# Top.net
KiCad netlist of a schematic drawn in Altium Designer
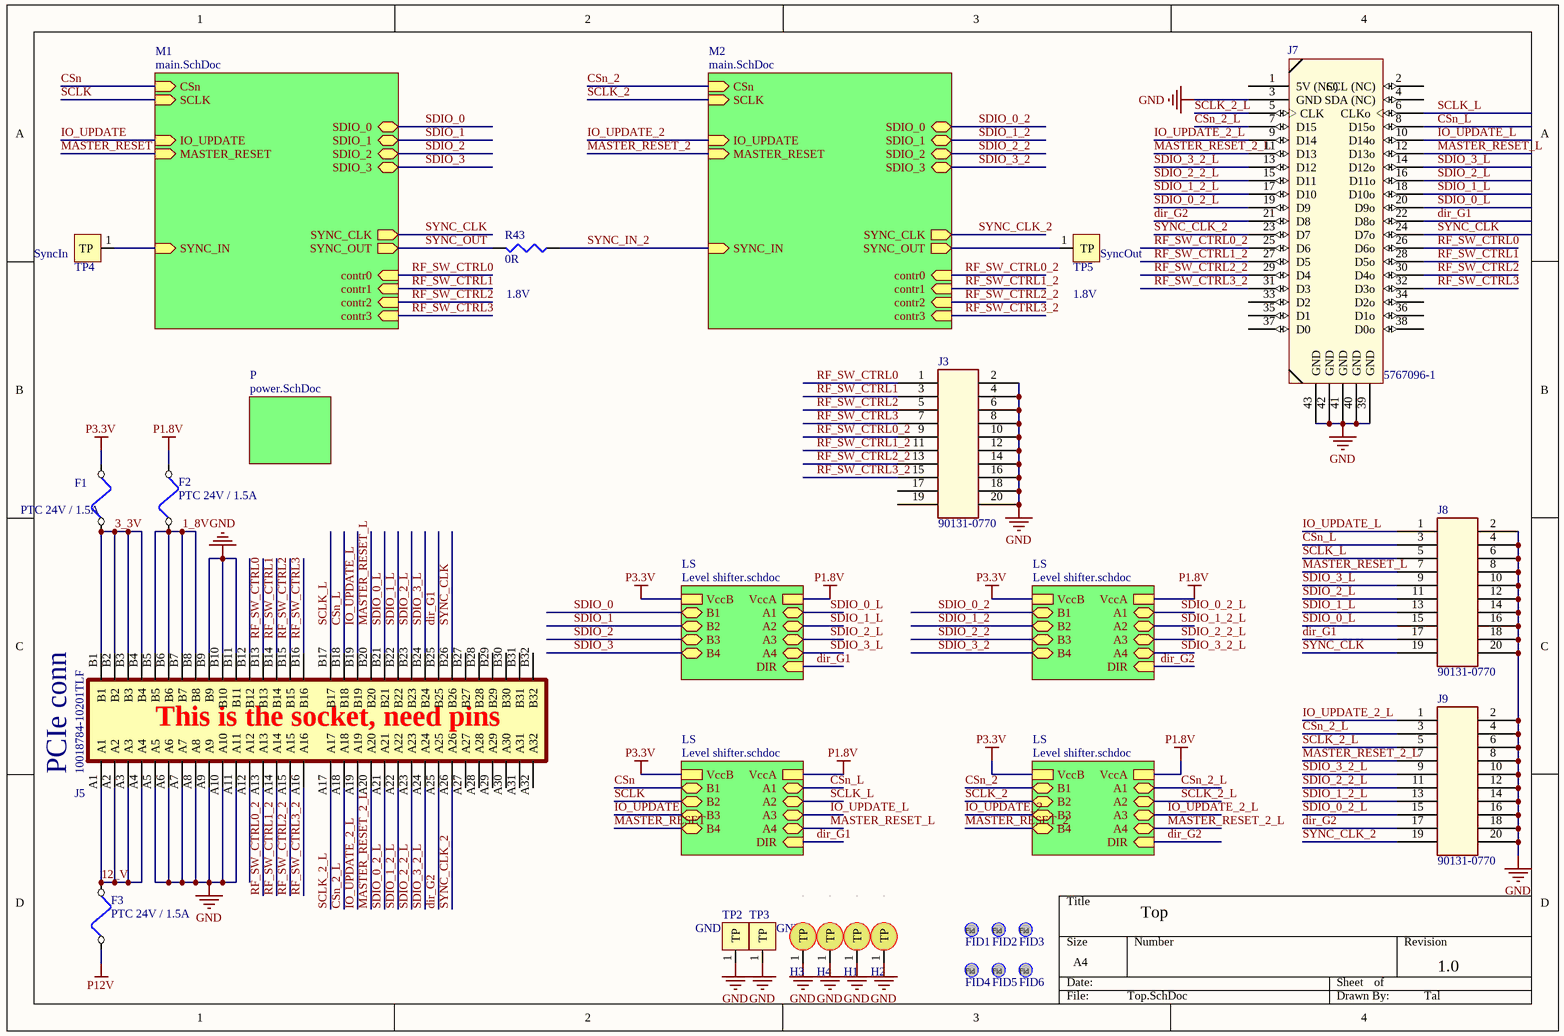
[diagram p0: Top.SchDoc]

(export (version "E")
  (design (tool "Eeschema 10.0.6"))
  (components
    (comp (ref "F1")
      (value "PTC 24V / 1.5A")
      (footprint "Landa_PCB:1812_F")
      (description "FUSE PTC 24V 1.5A POLYFUSE 1812")
      (fields
        (field (name "MANUFACTURER") "Littelfuse Inc")
        (field (name "MANUFACTURER PART NUMBER") "1812L150/24MR")
      )
      (libsource (lib "DPB_spliter") (part "1812L150/24MR"))
    )
    (comp (ref "F2")
      (value "PTC 24V / 1.5A")
      (footprint "Landa_PCB:1812_F")
      (description "FUSE PTC 24V 1.5A POLYFUSE 1812")
      (fields
        (field (name "MANUFACTURER") "Littelfuse Inc")
        (field (name "MANUFACTURER PART NUMBER") "1812L150/24MR")
      )
      (libsource (lib "DPB_spliter") (part "1812L150/24MR"))
    )
    (comp (ref "F3")
      (value "PTC 24V / 1.5A")
      (footprint "Landa_PCB:1812_F")
      (description "FUSE PTC 24V 1.5A POLYFUSE 1812")
      (fields
        (field (name "MANUFACTURER") "Littelfuse Inc")
        (field (name "MANUFACTURER PART NUMBER") "1812L150/24MR")
      )
      (libsource (lib "DPB_spliter") (part "1812L150/24MR"))
    )
    (comp (ref "FID1")
      (value "Fiducial")
      (footprint "Fiducial")
      (libsource (lib "DDS_PCB") (part "Fiducial"))
    )
    (comp (ref "FID2")
      (value "Fiducial")
      (footprint "Fiducial")
      (libsource (lib "DDS_PCB") (part "Fiducial"))
    )
    (comp (ref "FID3")
      (value "Fiducial")
      (footprint "Fiducial")
      (libsource (lib "DDS_PCB") (part "Fiducial"))
    )
    (comp (ref "FID4")
      (value "Fiducial")
      (footprint "Fiducial")
      (libsource (lib "DDS_PCB") (part "Fiducial"))
    )
    (comp (ref "FID5")
      (value "Fiducial")
      (footprint "Fiducial")
      (libsource (lib "DDS_PCB") (part "Fiducial"))
    )
    (comp (ref "FID6")
      (value "Fiducial")
      (footprint "Fiducial")
      (libsource (lib "DDS_PCB") (part "Fiducial"))
    )
    (comp (ref "H1")
      (value "Hole 3mm")
      (footprint "hole 3mm")
      (description "hole 3mm")
      (libsource (lib "L_SCH_Misc") (part "Hole 3mm"))
    )
    (comp (ref "H2")
      (value "Hole 3mm")
      (footprint "hole 3mm")
      (description "hole 3mm")
      (libsource (lib "L_SCH_Misc") (part "Hole 3mm"))
    )
    (comp (ref "H3")
      (value "Hole 3mm")
      (footprint "hole 3mm")
      (description "hole 3mm")
      (libsource (lib "L_SCH_Misc") (part "Hole 3mm"))
    )
    (comp (ref "H4")
      (value "Hole 3mm")
      (footprint "hole 3mm")
      (description "hole 3mm")
      (libsource (lib "L_SCH_Misc") (part "Hole 3mm"))
    )
    (comp (ref "J3")
      (value "90131-0770")
      (footprint "HEADER_10x2")
      (description "CONN HEADER 20 TH")
      (fields
        (field (name "MANUFACTURER") "Molex Connector Corporation")
        (field (name "MANUFACTURER PART NUMBER") "90131-0770")
      )
      (libsource (lib "L_SCH_J_Z") (part "90131-0770"))
    )
    (comp (ref "J5")
      (value "10018784-10201TLF")
      (footprint "PCIE_8LANE_EDGE")
      (description "64 Position Female Connector PCI Expressâ„¢ Gold 0.039 _1.00mm_ Black")
      (fields (field (name "MF") "Amphenol ICC"))
      (libsource (lib "10018784-10201TLF") (part "10018784-10201TLF"))
    )
    (comp (ref "J7")
      (value "5767096-1")
      (footprint "MICTOR-38_PIN")
      (description "CONN MICTOR 38POS .025 VERT SMD")
      (fields
        (field (name "MANUFACTURER") "TE Connectivity")
        (field (name "MANUFACTURER PART NUMBER") "5767096-1")
      )
      (libsource (lib "L_SCH_J_Z") (part "5767096-1"))
    )
    (comp (ref "J8")
      (value "90131-0770")
      (footprint "HEADER_10x2")
      (description "CONN HEADER 20 TH")
      (fields
        (field (name "MANUFACTURER") "Molex Connector Corporation")
        (field (name "MANUFACTURER PART NUMBER") "90131-0770")
      )
      (libsource (lib "L_SCH_J_Z") (part "90131-0770"))
    )
    (comp (ref "J9")
      (value "90131-0770")
      (footprint "HEADER_10x2")
      (description "CONN HEADER 20 TH")
      (fields
        (field (name "MANUFACTURER") "Molex Connector Corporation")
        (field (name "MANUFACTURER PART NUMBER") "90131-0770")
      )
      (libsource (lib "L_SCH_J_Z") (part "90131-0770"))
    )
    (comp (ref "R43")
      (value "0R")
      (footprint "R0402")
      (description "RES 0 OHM 1/10W 1% 0402 SMD")
      (fields
        (field (name "MANUFACTURER PART NUMBER") "ERJ-2RKF1000X")
        (field (name "MANUFACTURER") "Panasonic Electronic Components")
      )
      (libsource (lib "L_SCH_R") (part "RES 100 OHM 1/10W 1% 0402 SMD"))
    )
    (comp (ref "TP2")
      (value "GND")
      (footprint "Landa_PCB:TP_2x1.8")
      (description "TP PC MINIATURE SMT")
      (fields
        (field (name "MANUFACTURER") "Keystone Electronics")
        (field (name "MANUFACTURER PART NUMBER") "5015")
      )
      (libsource (lib "DPB_spliter") (part "TP mini_2"))
    )
    (comp (ref "TP3")
      (value "GND")
      (footprint "Landa_PCB:TP_2x1.8")
      (description "TP PC MINIATURE SMT")
      (fields
        (field (name "MANUFACTURER") "Keystone Electronics")
        (field (name "MANUFACTURER PART NUMBER") "5015")
      )
      (libsource (lib "DPB_spliter") (part "TP mini_1"))
    )
    (comp (ref "TP4")
      (value "SyncIn")
      (footprint "Landa_PCB:TP_2x1.8")
      (description "TP PC MINIATURE SMT")
      (fields
        (field (name "MANUFACTURER") "Keystone Electronics")
        (field (name "MANUFACTURER PART NUMBER") "5015")
      )
      (libsource (lib "") (part "TP mini_2_1"))
    )
    (comp (ref "TP5")
      (value "SyncOut")
      (footprint "Landa_PCB:TP_2x1.8")
      (description "TP PC MINIATURE SMT")
      (fields
        (field (name "MANUFACTURER") "Keystone Electronics")
        (field (name "MANUFACTURER PART NUMBER") "5015")
      )
      (libsource (lib "") (part "TP mini_2_2"))
    )
  )
  (nets
    (net (code "1") (name "/1_8V") (class "Default")
      (node (ref "F2") (pin "1") (pinfunction "1_1") (pintype "passive"))
      (node (ref "J5") (pin "B5") (pinfunction "B5_B5") (pintype "passive"))
      (node (ref "J5") (pin "B6") (pinfunction "B6_B6") (pintype "passive"))
      (node (ref "J5") (pin "B7") (pinfunction "B7_B7") (pintype "passive"))
      (node (ref "J5") (pin "B8") (pinfunction "B8_B8") (pintype "passive"))
    )
    (net (code "2") (name "/3_3V") (class "Default")
      (node (ref "F1") (pin "1") (pinfunction "1_1") (pintype "passive"))
      (node (ref "J5") (pin "B1") (pinfunction "B1_B1") (pintype "passive"))
      (node (ref "J5") (pin "B2") (pinfunction "B2_B2") (pintype "passive"))
      (node (ref "J5") (pin "B3") (pinfunction "B3_B3") (pintype "passive"))
      (node (ref "J5") (pin "B4") (pinfunction "B4_B4") (pintype "passive"))
    )
    (net (code "3") (name "/12_V") (class "Default")
      (node (ref "F3") (pin "2") (pinfunction "2_2") (pintype "passive"))
      (node (ref "J5") (pin "A1") (pinfunction "A1_A1") (pintype "passive"))
      (node (ref "J5") (pin "A2") (pinfunction "A2_A2") (pintype "passive"))
      (node (ref "J5") (pin "A3") (pinfunction "A3_A3") (pintype "passive"))
      (node (ref "J5") (pin "A4") (pinfunction "A4_A4") (pintype "passive"))
    )
    (net (code "6") (name "/CSn_2_L") (class "Default")
      (node (ref "J5") (pin "A18") (pinfunction "A18_A18") (pintype "passive"))
      (node (ref "J7") (pin "7") (pinfunction "D15_7") (pintype "bidirectional"))
      (node (ref "J9") (pin "3") (pinfunction "3_3") (pintype "passive"))
    )
    (net (code "7") (name "/CSn_L") (class "Default")
      (node (ref "J5") (pin "B18") (pinfunction "B18_B18") (pintype "passive"))
      (node (ref "J7") (pin "8") (pinfunction "D15o_8") (pintype "bidirectional"))
      (node (ref "J8") (pin "3") (pinfunction "3_3") (pintype "passive"))
    )
    (net (code "10") (name "/IO_UPDATE_2_L") (class "Default")
      (node (ref "J5") (pin "A19") (pinfunction "A19_A19") (pintype "passive"))
      (node (ref "J7") (pin "9") (pinfunction "D14_9") (pintype "bidirectional"))
      (node (ref "J9") (pin "1") (pinfunction "1_1") (pintype "passive"))
    )
    (net (code "11") (name "/IO_UPDATE_L") (class "Default")
      (node (ref "J5") (pin "B19") (pinfunction "B19_B19") (pintype "passive"))
      (node (ref "J7") (pin "10") (pinfunction "D14o_10") (pintype "bidirectional"))
      (node (ref "J8") (pin "1") (pinfunction "1_1") (pintype "passive"))
    )
    (net (code "14") (name "/MASTER_RESET_2_L") (class "Default")
      (node (ref "J5") (pin "A20") (pinfunction "A20_A20") (pintype "passive"))
      (node (ref "J7") (pin "11") (pinfunction "D13_11") (pintype "bidirectional"))
      (node (ref "J9") (pin "7") (pinfunction "7_7") (pintype "passive"))
    )
    (net (code "15") (name "/MASTER_RESET_L") (class "Default")
      (node (ref "J5") (pin "B20") (pinfunction "B20_B20") (pintype "passive"))
      (node (ref "J7") (pin "12") (pinfunction "D13o_12") (pintype "bidirectional"))
      (node (ref "J8") (pin "7") (pinfunction "7_7") (pintype "passive"))
    )
    (net (code "16") (name "/RF_SW_CTRL0") (class "Default")
      (node (ref "J3") (pin "1") (pinfunction "1_1") (pintype "passive"))
      (node (ref "J5") (pin "B13") (pinfunction "B13_B13") (pintype "passive"))
      (node (ref "J7") (pin "26") (pinfunction "D6o_26") (pintype "bidirectional"))
    )
    (net (code "17") (name "/RF_SW_CTRL0_2") (class "Default")
      (node (ref "J3") (pin "9") (pinfunction "9_9") (pintype "passive"))
      (node (ref "J5") (pin "A13") (pinfunction "A13_A13") (pintype "passive"))
      (node (ref "J7") (pin "25") (pinfunction "D6_25") (pintype "bidirectional"))
    )
    (net (code "18") (name "/RF_SW_CTRL1") (class "Default")
      (node (ref "J3") (pin "3") (pinfunction "3_3") (pintype "passive"))
      (node (ref "J5") (pin "B14") (pinfunction "B14_B14") (pintype "passive"))
      (node (ref "J7") (pin "28") (pinfunction "D5o_28") (pintype "bidirectional"))
    )
    (net (code "19") (name "/RF_SW_CTRL1_2") (class "Default")
      (node (ref "J3") (pin "11") (pinfunction "11_11") (pintype "passive"))
      (node (ref "J5") (pin "A14") (pinfunction "A14_A14") (pintype "passive"))
      (node (ref "J7") (pin "27") (pinfunction "D5_27") (pintype "bidirectional"))
    )
    (net (code "20") (name "/RF_SW_CTRL2") (class "Default")
      (node (ref "J3") (pin "5") (pinfunction "5_5") (pintype "passive"))
      (node (ref "J5") (pin "B15") (pinfunction "B15_B15") (pintype "passive"))
      (node (ref "J7") (pin "30") (pinfunction "D4o_30") (pintype "bidirectional"))
    )
    (net (code "21") (name "/RF_SW_CTRL2_2") (class "Default")
      (node (ref "J3") (pin "13") (pinfunction "13_13") (pintype "passive"))
      (node (ref "J5") (pin "A15") (pinfunction "A15_A15") (pintype "passive"))
      (node (ref "J7") (pin "29") (pinfunction "D4_29") (pintype "bidirectional"))
    )
    (net (code "22") (name "/RF_SW_CTRL3") (class "Default")
      (node (ref "J3") (pin "7") (pinfunction "7_7") (pintype "passive"))
      (node (ref "J5") (pin "B16") (pinfunction "B16_B16") (pintype "passive"))
      (node (ref "J7") (pin "32") (pinfunction "D3o_32") (pintype "bidirectional"))
    )
    (net (code "23") (name "/RF_SW_CTRL3_2") (class "Default")
      (node (ref "J3") (pin "15") (pinfunction "15_15") (pintype "passive"))
      (node (ref "J5") (pin "A16") (pinfunction "A16_A16") (pintype "passive"))
      (node (ref "J7") (pin "31") (pinfunction "D3_31") (pintype "bidirectional"))
    )
    (net (code "26") (name "/SCLK_2_L") (class "Default")
      (node (ref "J5") (pin "A17") (pinfunction "A17_A17") (pintype "passive"))
      (node (ref "J7") (pin "5") (pinfunction "CLK_5") (pintype "bidirectional"))
      (node (ref "J9") (pin "5") (pinfunction "5_5") (pintype "passive"))
    )
    (net (code "27") (name "/SCLK_L") (class "Default")
      (node (ref "J5") (pin "B17") (pinfunction "B17_B17") (pintype "passive"))
      (node (ref "J7") (pin "6") (pinfunction "CLKo_6") (pintype "bidirectional"))
      (node (ref "J8") (pin "5") (pinfunction "5_5") (pintype "passive"))
    )
    (net (code "30") (name "/SDIO_0_2_L") (class "Default")
      (node (ref "J5") (pin "A21") (pinfunction "A21_A21") (pintype "passive"))
      (node (ref "J7") (pin "19") (pinfunction "D9_19") (pintype "bidirectional"))
      (node (ref "J9") (pin "15") (pinfunction "15_15") (pintype "passive"))
    )
    (net (code "31") (name "/SDIO_0_L") (class "Default")
      (node (ref "J5") (pin "B21") (pinfunction "B21_B21") (pintype "passive"))
      (node (ref "J7") (pin "20") (pinfunction "D9o_20") (pintype "bidirectional"))
      (node (ref "J8") (pin "15") (pinfunction "15_15") (pintype "passive"))
    )
    (net (code "34") (name "/SDIO_1_2_L") (class "Default")
      (node (ref "J5") (pin "A22") (pinfunction "A22_A22") (pintype "passive"))
      (node (ref "J7") (pin "17") (pinfunction "D10_17") (pintype "bidirectional"))
      (node (ref "J9") (pin "13") (pinfunction "13_13") (pintype "passive"))
    )
    (net (code "35") (name "/SDIO_1_L") (class "Default")
      (node (ref "J5") (pin "B22") (pinfunction "B22_B22") (pintype "passive"))
      (node (ref "J7") (pin "18") (pinfunction "D10o_18") (pintype "bidirectional"))
      (node (ref "J8") (pin "13") (pinfunction "13_13") (pintype "passive"))
    )
    (net (code "38") (name "/SDIO_2_2_L") (class "Default")
      (node (ref "J5") (pin "A23") (pinfunction "A23_A23") (pintype "passive"))
      (node (ref "J7") (pin "15") (pinfunction "D11_15") (pintype "bidirectional"))
      (node (ref "J9") (pin "11") (pinfunction "11_11") (pintype "passive"))
    )
    (net (code "39") (name "/SDIO_2_L") (class "Default")
      (node (ref "J5") (pin "B23") (pinfunction "B23_B23") (pintype "passive"))
      (node (ref "J7") (pin "16") (pinfunction "D11o_16") (pintype "bidirectional"))
      (node (ref "J8") (pin "11") (pinfunction "11_11") (pintype "passive"))
    )
    (net (code "42") (name "/SDIO_3_2_L") (class "Default")
      (node (ref "J5") (pin "A24") (pinfunction "A24_A24") (pintype "passive"))
      (node (ref "J7") (pin "13") (pinfunction "D12_13") (pintype "bidirectional"))
      (node (ref "J9") (pin "9") (pinfunction "9_9") (pintype "passive"))
    )
    (net (code "43") (name "/SDIO_3_L") (class "Default")
      (node (ref "J5") (pin "B24") (pinfunction "B24_B24") (pintype "passive"))
      (node (ref "J7") (pin "14") (pinfunction "D12o_14") (pintype "bidirectional"))
      (node (ref "J8") (pin "9") (pinfunction "9_9") (pintype "passive"))
    )
    (net (code "44") (name "/SYNC_CLK") (class "Default")
      (node (ref "J5") (pin "B26") (pinfunction "B26_B26") (pintype "passive"))
      (node (ref "J7") (pin "24") (pinfunction "D7o_24") (pintype "bidirectional"))
      (node (ref "J8") (pin "19") (pinfunction "19_19") (pintype "passive"))
    )
    (net (code "45") (name "/SYNC_CLK_2") (class "Default")
      (node (ref "J5") (pin "A26") (pinfunction "A26_A26") (pintype "passive"))
      (node (ref "J7") (pin "23") (pinfunction "D7_23") (pintype "bidirectional"))
      (node (ref "J9") (pin "19") (pinfunction "19_19") (pintype "passive"))
    )
    (net (code "46") (name "/SYNC_IN") (class "Default")
      (node (ref "TP4") (pin "1") (pinfunction "TP_1") (pintype "passive"))
    )
    (net (code "47") (name "/SYNC_IN_2") (class "Default")
      (node (ref "R43") (pin "1") (pinfunction "1_1") (pintype "passive"))
    )
    (net (code "48") (name "/SYNC_OUT") (class "Default")
      (node (ref "R43") (pin "2") (pinfunction "2_2") (pintype "passive"))
    )
    (net (code "49") (name "/SYNC_OUT_1") (class "Default")
      (node (ref "TP5") (pin "1") (pinfunction "TP_1") (pintype "passive"))
    )
    (net (code "50") (name "/dir_G1") (class "Default")
      (node (ref "J5") (pin "B25") (pinfunction "B25_B25") (pintype "passive"))
      (node (ref "J7") (pin "22") (pinfunction "D8o_22") (pintype "bidirectional"))
      (node (ref "J8") (pin "17") (pinfunction "17_17") (pintype "passive"))
    )
    (net (code "51") (name "/dir_G2") (class "Default")
      (node (ref "J5") (pin "A25") (pinfunction "A25_A25") (pintype "passive"))
      (node (ref "J7") (pin "21") (pinfunction "D8_21") (pintype "bidirectional"))
      (node (ref "J9") (pin "17") (pinfunction "17_17") (pintype "passive"))
    )
    (net (code "52") (name "GND") (class "Default")
      (node (ref "H1") (pin "1") (pinfunction "TP_1") (pintype "passive"))
      (node (ref "H2") (pin "1") (pinfunction "TP_1") (pintype "passive"))
      (node (ref "H3") (pin "1") (pinfunction "TP_1") (pintype "passive"))
      (node (ref "H4") (pin "1") (pinfunction "TP_1") (pintype "passive"))
      (node (ref "J3") (pin "10") (pinfunction "10_10") (pintype "passive"))
      (node (ref "J3") (pin "12") (pinfunction "12_12") (pintype "passive"))
      (node (ref "J3") (pin "14") (pinfunction "14_14") (pintype "passive"))
      (node (ref "J3") (pin "16") (pinfunction "16_16") (pintype "passive"))
      (node (ref "J3") (pin "18") (pinfunction "18_18") (pintype "passive"))
      (node (ref "J3") (pin "2") (pinfunction "2_2") (pintype "passive"))
      (node (ref "J3") (pin "20") (pinfunction "20_20") (pintype "passive"))
      (node (ref "J3") (pin "4") (pinfunction "4_4") (pintype "passive"))
      (node (ref "J3") (pin "6") (pinfunction "6_6") (pintype "passive"))
      (node (ref "J3") (pin "8") (pinfunction "8_8") (pintype "passive"))
      (node (ref "J5") (pin "A10") (pinfunction "A10_A10") (pintype "passive"))
      (node (ref "J5") (pin "A11") (pinfunction "A11_A11") (pintype "passive"))
      (node (ref "J5") (pin "A5") (pinfunction "A5_A5") (pintype "passive"))
      (node (ref "J5") (pin "A6") (pinfunction "A6_A6") (pintype "passive"))
      (node (ref "J5") (pin "A7") (pinfunction "A7_A7") (pintype "passive"))
      (node (ref "J5") (pin "A8") (pinfunction "A8_A8") (pintype "passive"))
      (node (ref "J5") (pin "A9") (pinfunction "A9_A9") (pintype "passive"))
      (node (ref "J5") (pin "B10") (pinfunction "B10_B10") (pintype "passive"))
      (node (ref "J5") (pin "B11") (pinfunction "B11_B11") (pintype "passive"))
      (node (ref "J5") (pin "B9") (pinfunction "B9_B9") (pintype "passive"))
      (node (ref "J7") (pin "3") (pinfunction "GND_3") (pintype "power_in"))
      (node (ref "J7") (pin "39") (pinfunction "GND_39") (pintype "power_in"))
      (node (ref "J7") (pin "40") (pinfunction "GND_40") (pintype "power_in"))
      (node (ref "J7") (pin "41") (pinfunction "GND_41") (pintype "power_in"))
      (node (ref "J7") (pin "42") (pinfunction "GND_42") (pintype "power_in"))
      (node (ref "J7") (pin "43") (pinfunction "GND_43") (pintype "power_in"))
      (node (ref "J8") (pin "10") (pinfunction "10_10") (pintype "passive"))
      (node (ref "J8") (pin "12") (pinfunction "12_12") (pintype "passive"))
      (node (ref "J8") (pin "14") (pinfunction "14_14") (pintype "passive"))
      (node (ref "J8") (pin "16") (pinfunction "16_16") (pintype "passive"))
      (node (ref "J8") (pin "18") (pinfunction "18_18") (pintype "passive"))
      (node (ref "J8") (pin "2") (pinfunction "2_2") (pintype "passive"))
      (node (ref "J8") (pin "20") (pinfunction "20_20") (pintype "passive"))
      (node (ref "J8") (pin "4") (pinfunction "4_4") (pintype "passive"))
      (node (ref "J8") (pin "6") (pinfunction "6_6") (pintype "passive"))
      (node (ref "J8") (pin "8") (pinfunction "8_8") (pintype "passive"))
      (node (ref "J9") (pin "10") (pinfunction "10_10") (pintype "passive"))
      (node (ref "J9") (pin "12") (pinfunction "12_12") (pintype "passive"))
      (node (ref "J9") (pin "14") (pinfunction "14_14") (pintype "passive"))
      (node (ref "J9") (pin "16") (pinfunction "16_16") (pintype "passive"))
      (node (ref "J9") (pin "18") (pinfunction "18_18") (pintype "passive"))
      (node (ref "J9") (pin "2") (pinfunction "2_2") (pintype "passive"))
      (node (ref "J9") (pin "20") (pinfunction "20_20") (pintype "passive"))
      (node (ref "J9") (pin "4") (pinfunction "4_4") (pintype "passive"))
      (node (ref "J9") (pin "6") (pinfunction "6_6") (pintype "passive"))
      (node (ref "J9") (pin "8") (pinfunction "8_8") (pintype "passive"))
      (node (ref "TP2") (pin "1") (pinfunction "TP_1") (pintype "passive"))
      (node (ref "TP3") (pin "1") (pinfunction "TP_1") (pintype "passive"))
    )
    (net (code "53") (name "P1.8V") (class "Default")
      (node (ref "F2") (pin "2") (pinfunction "2_2") (pintype "passive"))
    )
    (net (code "54") (name "P3.3V") (class "Default")
      (node (ref "F1") (pin "2") (pinfunction "2_2") (pintype "passive"))
    )
    (net (code "55") (name "P12V") (class "Default")
      (node (ref "F3") (pin "1") (pinfunction "1_1") (pintype "passive"))
    )
    (net (code "56") (name "unconnected-(J3-Pad17)") (class "Default")
      (node (ref "J3") (pin "17") (pinfunction "17_17") (pintype "passive"))
    )
    (net (code "57") (name "unconnected-(J3-Pad19)") (class "Default")
      (node (ref "J3") (pin "19") (pinfunction "19_19") (pintype "passive"))
    )
    (net (code "58") (name "unconnected-(J5-PadA12)") (class "Default")
      (node (ref "J5") (pin "A12") (pinfunction "A12_A12") (pintype "passive"))
    )
    (net (code "59") (name "unconnected-(J5-PadA27)") (class "Default")
      (node (ref "J5") (pin "A27") (pinfunction "A27_A27") (pintype "passive"))
    )
    (net (code "60") (name "unconnected-(J5-PadA28)") (class "Default")
      (node (ref "J5") (pin "A28") (pinfunction "A28_A28") (pintype "passive"))
    )
    (net (code "61") (name "unconnected-(J5-PadA29)") (class "Default")
      (node (ref "J5") (pin "A29") (pinfunction "A29_A29") (pintype "passive"))
    )
    (net (code "62") (name "unconnected-(J5-PadA30)") (class "Default")
      (node (ref "J5") (pin "A30") (pinfunction "A30_A30") (pintype "passive"))
    )
    (net (code "63") (name "unconnected-(J5-PadA31)") (class "Default")
      (node (ref "J5") (pin "A31") (pinfunction "A31_A31") (pintype "passive"))
    )
    (net (code "64") (name "unconnected-(J5-PadA32)") (class "Default")
      (node (ref "J5") (pin "A32") (pinfunction "A32_A32") (pintype "passive"))
    )
    (net (code "65") (name "unconnected-(J5-PadB12)") (class "Default")
      (node (ref "J5") (pin "B12") (pinfunction "B12_B12") (pintype "passive"))
    )
    (net (code "66") (name "unconnected-(J5-PadB27)") (class "Default")
      (node (ref "J5") (pin "B27") (pinfunction "B27_B27") (pintype "passive"))
    )
    (net (code "67") (name "unconnected-(J5-PadB28)") (class "Default")
      (node (ref "J5") (pin "B28") (pinfunction "B28_B28") (pintype "passive"))
    )
    (net (code "68") (name "unconnected-(J5-PadB29)") (class "Default")
      (node (ref "J5") (pin "B29") (pinfunction "B29_B29") (pintype "passive"))
    )
    (net (code "69") (name "unconnected-(J5-PadB30)") (class "Default")
      (node (ref "J5") (pin "B30") (pinfunction "B30_B30") (pintype "passive"))
    )
    (net (code "70") (name "unconnected-(J5-PadB31)") (class "Default")
      (node (ref "J5") (pin "B31") (pinfunction "B31_B31") (pintype "passive"))
    )
    (net (code "71") (name "unconnected-(J5-PadB32)") (class "Default")
      (node (ref "J5") (pin "B32") (pinfunction "B32_B32") (pintype "passive"))
    )
    (net (code "72") (name "unconnected-(J7-5V_(NC)-Pad1)") (class "Default")
      (node (ref "J7") (pin "1") (pinfunction "5V_(NC)_1") (pintype "power_in"))
    )
    (net (code "73") (name "unconnected-(J7-D0-Pad37)") (class "Default")
      (node (ref "J7") (pin "37") (pinfunction "D0_37") (pintype "bidirectional"))
    )
    (net (code "74") (name "unconnected-(J7-D0o-Pad38)") (class "Default")
      (node (ref "J7") (pin "38") (pinfunction "D0o_38") (pintype "bidirectional"))
    )
    (net (code "75") (name "unconnected-(J7-D1-Pad35)") (class "Default")
      (node (ref "J7") (pin "35") (pinfunction "D1_35") (pintype "bidirectional"))
    )
    (net (code "76") (name "unconnected-(J7-D1o-Pad36)") (class "Default")
      (node (ref "J7") (pin "36") (pinfunction "D1o_36") (pintype "bidirectional"))
    )
    (net (code "77") (name "unconnected-(J7-D2-Pad33)") (class "Default")
      (node (ref "J7") (pin "33") (pinfunction "D2_33") (pintype "bidirectional"))
    )
    (net (code "78") (name "unconnected-(J7-D2o-Pad34)") (class "Default")
      (node (ref "J7") (pin "34") (pinfunction "D2o_34") (pintype "bidirectional"))
    )
    (net (code "79") (name "unconnected-(J7-SCL_(NC)-Pad2)") (class "Default")
      (node (ref "J7") (pin "2") (pinfunction "SCL_(NC)_2") (pintype "bidirectional"))
    )
    (net (code "80") (name "unconnected-(J7-SDA_(NC)-Pad4)") (class "Default")
      (node (ref "J7") (pin "4") (pinfunction "SDA_(NC)_4") (pintype "bidirectional"))
    )
  )
)
